# SCH_Usb-Hub_2025-03-01.net
KiCad netlist of a schematic drawn in EasyEDA
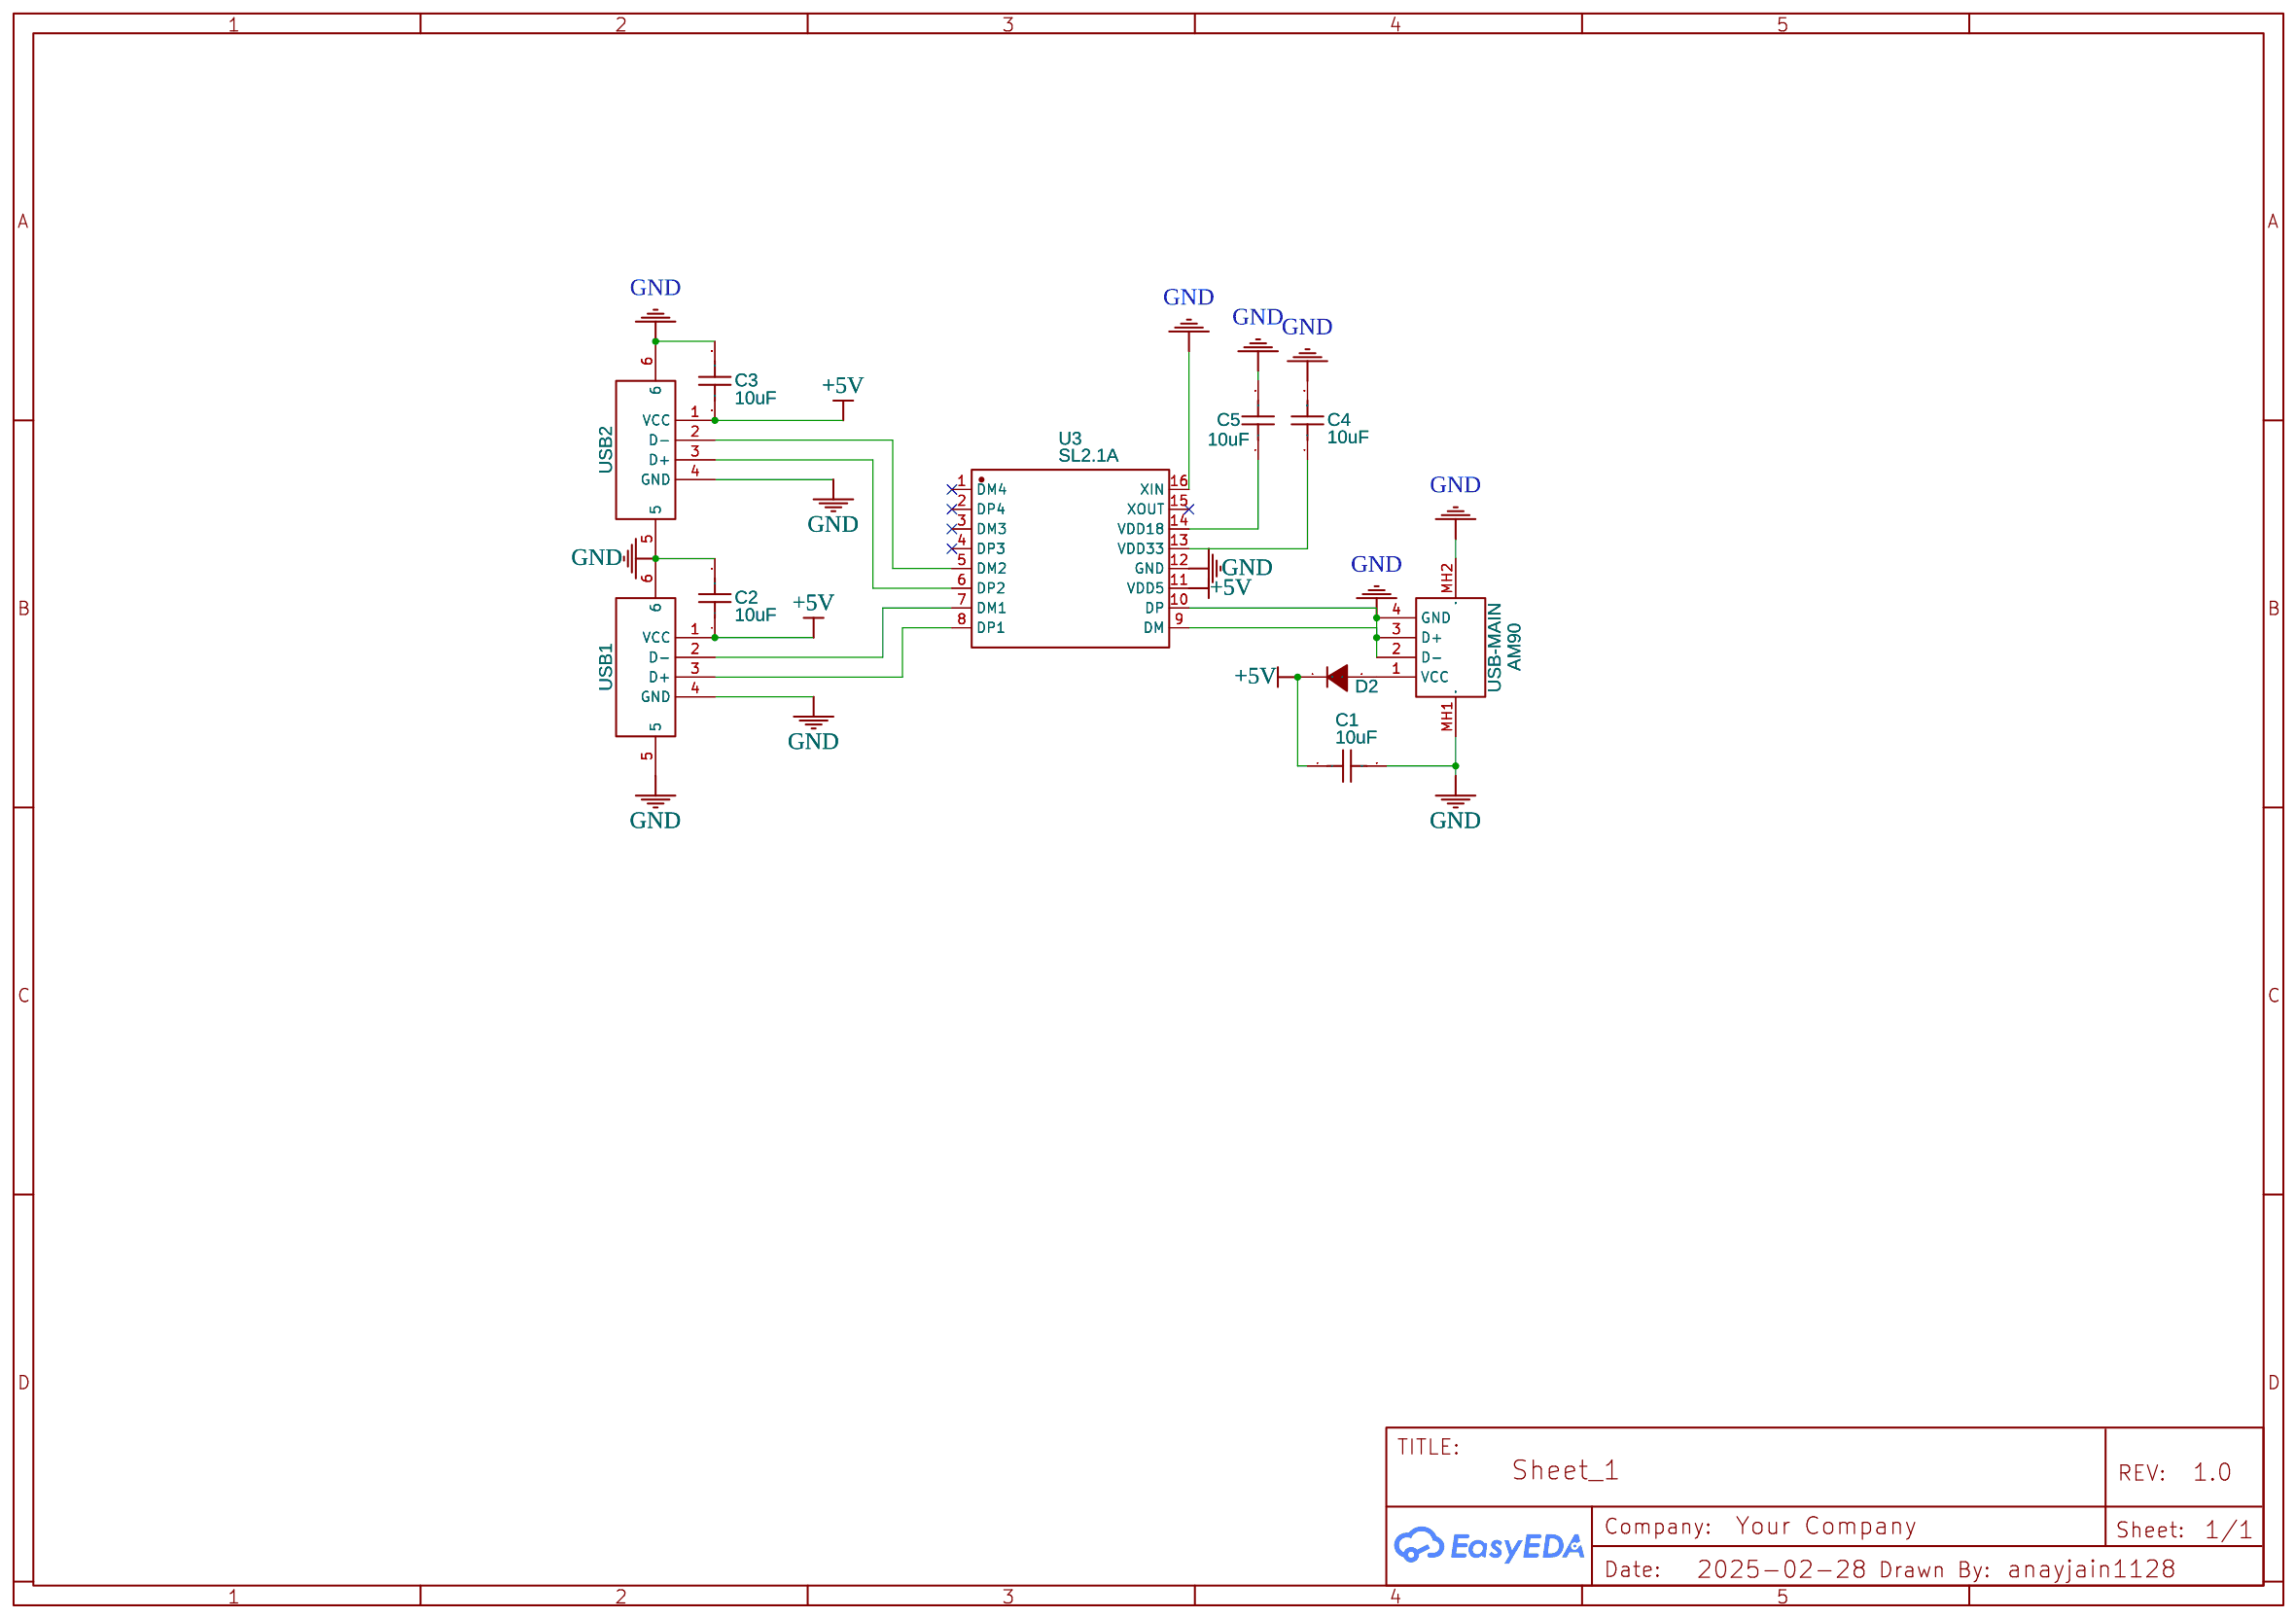
[diagram p0: schematic sheet]

(export (version "E")
  (design (tool "Eeschema 10.0.6"))
  (components
    (comp (ref "C1")
      (value "10uF")
      (fields
        (field (name "Manufacturer Part") "CL10A106KP8NNNC")
        (field (name "Manufacturer") "SAMSUNG(三星)")
      )
      (libsource (lib "") (part "CL10A106KP8NNNC_1"))
    )
    (comp (ref "C2")
      (value "10uF")
      (fields
        (field (name "Manufacturer Part") "CL10A106KP8NNNC")
        (field (name "Manufacturer") "SAMSUNG(三星)")
      )
      (libsource (lib "") (part "CL10A106KP8NNNC"))
    )
    (comp (ref "C3")
      (value "10uF")
      (fields
        (field (name "Manufacturer Part") "CL10A106KP8NNNC")
        (field (name "Manufacturer") "SAMSUNG(三星)")
      )
      (libsource (lib "") (part "CL10A106KP8NNNC"))
    )
    (comp (ref "C4")
      (value "10uF")
      (fields
        (field (name "Manufacturer Part") "CL10A106KP8NNNC")
        (field (name "Manufacturer") "SAMSUNG(三星)")
      )
      (libsource (lib "") (part "CL10A106KP8NNNC"))
    )
    (comp (ref "C5")
      (value "10uF")
      (fields
        (field (name "Manufacturer Part") "CL10A106KP8NNNC")
        (field (name "Manufacturer") "SAMSUNG(三星)")
      )
      (libsource (lib "") (part "CL10A106KP8NNNC"))
    )
    (comp (ref "D2")
      (value "NSR0320MW2T1G")
      (fields (field (name "Manufacturer") "onsemi(安森美)"))
      (libsource (lib "") (part "NSR0320MW2T1G"))
    )
    (comp (ref "U3")
      (value "SL2.1A")
      (fields (field (name "Manufacturer") "CoreChips(和芯润德)"))
      (libsource (lib "") (part "SL2.1A"))
    )
    (comp (ref "USB-MAIN")
      (value "AM90")
      (fields (field (name "Manufacturer") "SHOU HAN(首韩)"))
      (libsource (lib "") (part "AM90"))
    )
    (comp (ref "USB1")
      (value "USB-AF-90-14.4X13.6-H7.0-DIP")
      (fields (field (name "Manufacturer Part") "903-131A1011D10100") (field (name "Manufacturer") "精拓金"))
      (libsource (lib "") (part "USB-AF-90-14.4X13.6-H7.0-DIP"))
    )
    (comp (ref "USB2")
      (value "USB-AF-90-14.4X13.6-H7.0-DIP")
      (fields (field (name "Manufacturer Part") "903-131A1011D10100") (field (name "Manufacturer") "精拓金"))
      (libsource (lib "") (part "USB-AF-90-14.4X13.6-H7.0-DIP"))
    )
  )
  (nets
    (net (code "1") (name "+5V") (class "Default")
      (node (ref "C1") (pin "1") (pinfunction "1_1") (pintype "unspecified"))
      (node (ref "C2") (pin "1") (pinfunction "1_1") (pintype "unspecified"))
      (node (ref "C3") (pin "1") (pinfunction "1_1") (pintype "unspecified"))
      (node (ref "D2") (pin "1") (pinfunction "C_1") (pintype "unspecified"))
      (node (ref "U3") (pin "11") (pinfunction "VDD5_11") (pintype "unspecified"))
      (node (ref "USB1") (pin "1") (pinfunction "VCC_1") (pintype "unspecified"))
      (node (ref "USB2") (pin "1") (pinfunction "VCC_1") (pintype "unspecified"))
    )
    (net (code "2") (name "GND") (class "Default")
      (node (ref "C1") (pin "2") (pinfunction "2_2") (pintype "unspecified"))
      (node (ref "C2") (pin "2") (pinfunction "2_2") (pintype "unspecified"))
      (node (ref "C3") (pin "2") (pinfunction "2_2") (pintype "unspecified"))
      (node (ref "C4") (pin "2") (pinfunction "2_2") (pintype "unspecified"))
      (node (ref "C5") (pin "2") (pinfunction "2_2") (pintype "unspecified"))
      (node (ref "U3") (pin "10") (pinfunction "DP_10") (pintype "unspecified"))
      (node (ref "U3") (pin "12") (pinfunction "GND_12") (pintype "unspecified"))
      (node (ref "U3") (pin "16") (pinfunction "XIN_16") (pintype "unspecified"))
      (node (ref "U3") (pin "9") (pinfunction "DM_9") (pintype "unspecified"))
      (node (ref "USB-MAIN") (pin "2") (pinfunction "D-_2") (pintype "input"))
      (node (ref "USB-MAIN") (pin "3") (pinfunction "D+_3") (pintype "input"))
      (node (ref "USB-MAIN") (pin "4") (pinfunction "GND_4") (pintype "input"))
      (node (ref "USB-MAIN") (pin "MH1") (pinfunction "MH1_MH1") (pintype "unspecified"))
      (node (ref "USB-MAIN") (pin "MH2") (pinfunction "MH2_MH2") (pintype "unspecified"))
      (node (ref "USB1") (pin "4") (pinfunction "GND_4") (pintype "unspecified"))
      (node (ref "USB1") (pin "5") (pinfunction "5_5") (pintype "unspecified"))
      (node (ref "USB1") (pin "6") (pinfunction "6_6") (pintype "unspecified"))
      (node (ref "USB2") (pin "4") (pinfunction "GND_4") (pintype "unspecified"))
      (node (ref "USB2") (pin "5") (pinfunction "5_5") (pintype "unspecified"))
      (node (ref "USB2") (pin "6") (pinfunction "6_6") (pintype "unspecified"))
    )
    (net (code "3") (name "Net-(D2-A)") (class "Default")
      (node (ref "D2") (pin "2") (pinfunction "A_2") (pintype "unspecified"))
      (node (ref "USB-MAIN") (pin "1") (pinfunction "VCC_1") (pintype "input"))
    )
    (net (code "4") (name "Net-(U3-DM1)") (class "Default")
      (node (ref "U3") (pin "7") (pinfunction "DM1_7") (pintype "unspecified"))
      (node (ref "USB1") (pin "2") (pinfunction "D-_2") (pintype "unspecified"))
    )
    (net (code "5") (name "Net-(U3-DM2)") (class "Default")
      (node (ref "U3") (pin "5") (pinfunction "DM2_5") (pintype "unspecified"))
      (node (ref "USB2") (pin "2") (pinfunction "D-_2") (pintype "unspecified"))
    )
    (net (code "6") (name "Net-(U3-DP1)") (class "Default")
      (node (ref "U3") (pin "8") (pinfunction "DP1_8") (pintype "unspecified"))
      (node (ref "USB1") (pin "3") (pinfunction "D+_3") (pintype "unspecified"))
    )
    (net (code "7") (name "Net-(U3-DP2)") (class "Default")
      (node (ref "U3") (pin "6") (pinfunction "DP2_6") (pintype "unspecified"))
      (node (ref "USB2") (pin "3") (pinfunction "D+_3") (pintype "unspecified"))
    )
    (net (code "8") (name "Net-(U3-VDD18)") (class "Default")
      (node (ref "C5") (pin "1") (pinfunction "1_1") (pintype "unspecified"))
      (node (ref "U3") (pin "14") (pinfunction "VDD18_14") (pintype "unspecified"))
    )
    (net (code "9") (name "Net-(U3-VDD33)") (class "Default")
      (node (ref "C4") (pin "1") (pinfunction "1_1") (pintype "unspecified"))
      (node (ref "U3") (pin "13") (pinfunction "VDD33_13") (pintype "unspecified"))
    )
    (net (code "10") (name "unconnected-(U3-DM3-Pad3)") (class "Default")
      (node (ref "U3") (pin "3") (pinfunction "DM3_3") (pintype "unspecified+no_connect"))
    )
    (net (code "11") (name "unconnected-(U3-DM4-Pad1)") (class "Default")
      (node (ref "U3") (pin "1") (pinfunction "DM4_1") (pintype "unspecified+no_connect"))
    )
    (net (code "12") (name "unconnected-(U3-DP3-Pad4)") (class "Default")
      (node (ref "U3") (pin "4") (pinfunction "DP3_4") (pintype "unspecified+no_connect"))
    )
    (net (code "13") (name "unconnected-(U3-DP4-Pad2)") (class "Default")
      (node (ref "U3") (pin "2") (pinfunction "DP4_2") (pintype "unspecified+no_connect"))
    )
    (net (code "14") (name "unconnected-(U3-XOUT-Pad15)") (class "Default")
      (node (ref "U3") (pin "15") (pinfunction "XOUT_15") (pintype "unspecified+no_connect"))
    )
  )
)
